# Analog_Telem.net
KiCad netlist of a schematic drawn in Altium Designer
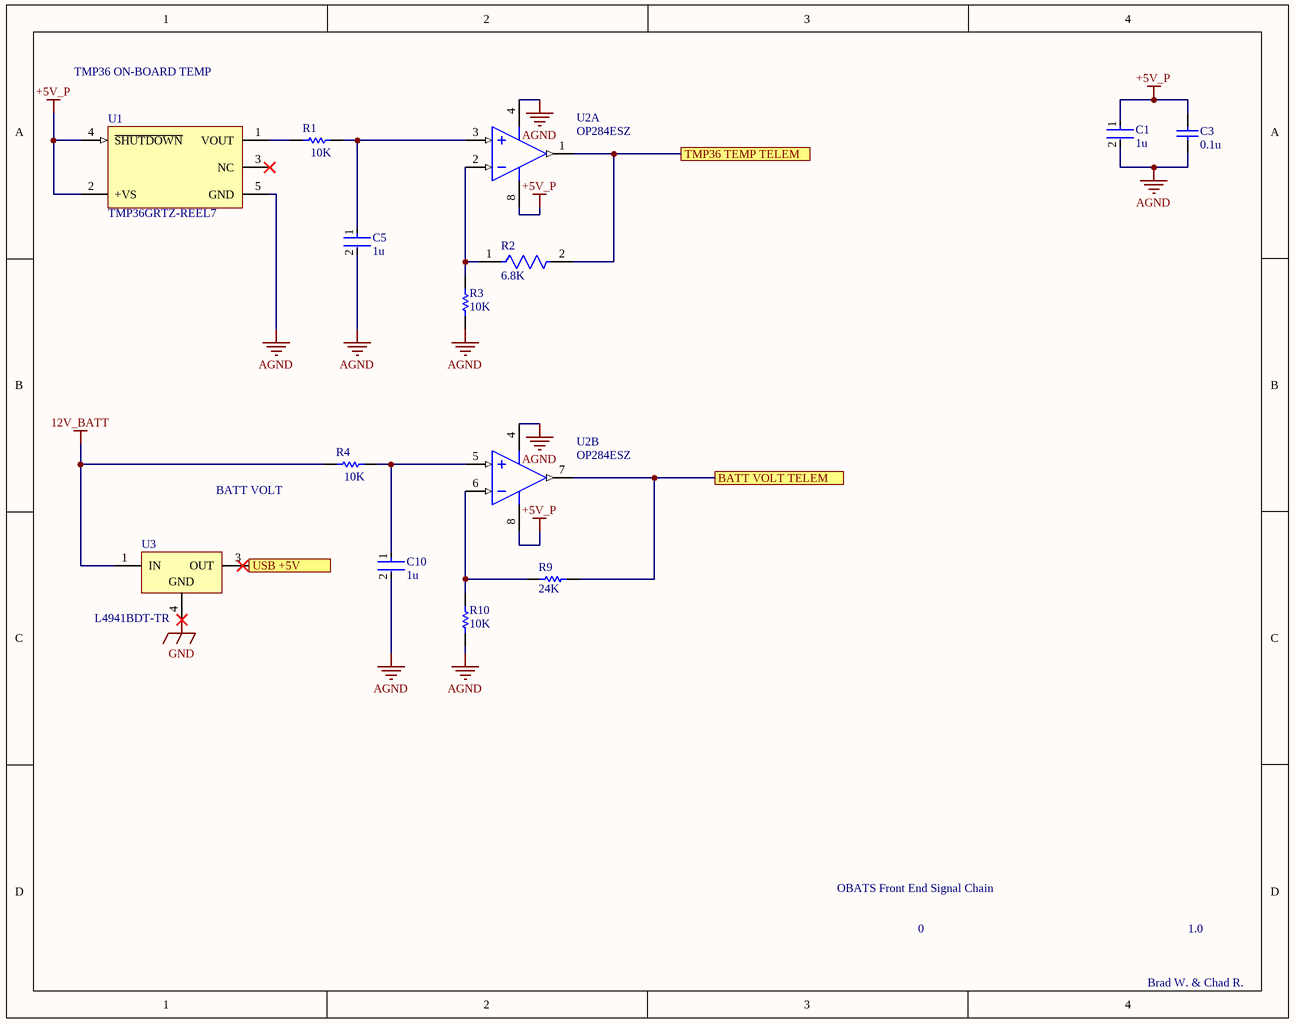
[diagram p0: Analog_Telem.SchDoc]

(export (version "E")
  (design (tool "Eeschema 10.0.6"))
  (components
    (comp (ref "C1")
      (value "1u")
      (footprint "FP-CL31-IPC_B")
      (description "Cap Ceramic 1uF 50V X7R ±10% SMD 1206 +125°C Embossed T/R")
      (fields (field (name "VOLTAGE") "50V") (field (name "TOLERANCE") "10%"))
      (libsource (lib "Altium Content Vault") (part "b4654b650e69147ec39a6b967a45e02"))
    )
    (comp (ref "C3")
      (value "0.1u")
      (footprint "CAPC1206(3216)130_M")
      (description "CAP 100nF 100V ±20% 1206 (3216 Metric) Thickness 1.3mm SMD")
      (fields (field (name "TOLERANCE") "Â±20%"))
      (libsource (lib "Altium Content Vault") (part "CAP"))
    )
    (comp (ref "C5")
      (value "1u")
      (footprint "FP-CL31-IPC_B")
      (description "Cap Ceramic 1uF 50V X7R ±10% SMD 1206 +125°C Embossed T/R")
      (fields (field (name "VOLTAGE") "50V") (field (name "TOLERANCE") "10%"))
      (libsource (lib "Altium Content Vault") (part "b4654b650e69147ec39a6b967a45e02"))
    )
    (comp (ref "C10")
      (value "1u")
      (footprint "FP-CL31-IPC_B")
      (description "Cap Ceramic 1uF 50V X7R ±10% SMD 1206 +125°C Embossed T/R")
      (fields (field (name "VOLTAGE") "50V") (field (name "TOLERANCE") "10%"))
      (libsource (lib "Altium Content Vault") (part "b4654b650e69147ec39a6b967a45e02"))
    )
    (comp (ref "R1")
      (value "10K")
      (footprint "RESC3116X65X45ML10T20")
      (fields (field (name "MANUFACTURER") "Yageo") (field (name "PART NUMBER") "AC1206FR-0710KL"))
      (libsource (lib "Altium Content Vault") (part "RES"))
    )
    (comp (ref "R2")
      (value "6.8K")
      (footprint "FP-AC1206-MFG")
      (description "RES SMD 6.8K OHM 1% 1/4W 1206")
      (fields
        (field (name "OCTOPART") "https://octopart.com/ac1206fr-076k8l-yageo-26041203")
        (field (name "MANUFACTURER PART NUMBER") "AC1206FR-076K8L")
      )
      (libsource (lib "Altium Content Vault") (part "1029c3af85768c4190bb7ad29bc67b5"))
    )
    (comp (ref "R3")
      (value "10K")
      (footprint "RESC3116X65X45ML10T20")
      (fields (field (name "MANUFACTURER") "Yageo") (field (name "PART NUMBER") "AC1206FR-0710KL"))
      (libsource (lib "Altium Content Vault") (part "RES"))
    )
    (comp (ref "R4")
      (value "10K")
      (footprint "RESC3116X65X45ML10T20")
      (fields (field (name "MANUFACTURER") "Yageo") (field (name "PART NUMBER") "AC1206FR-0710KL"))
      (libsource (lib "Altium Content Vault") (part "RES"))
    )
    (comp (ref "R9")
      (value "24K")
      (footprint "RESC2013X70X40ML20T20")
      (fields (field (name "MANUFACTURER") "Panasonic") (field (name "PART NUMBER") "ERJ6ENF2402V"))
      (libsource (lib "Altium Content Vault") (part "RES"))
    )
    (comp (ref "R10")
      (value "10K")
      (footprint "RESC3116X65X45ML10T20")
      (fields (field (name "MANUFACTURER") "Yageo") (field (name "PART NUMBER") "AC1206FR-0710KL"))
      (libsource (lib "Altium Content Vault") (part "RES"))
    )
    (comp (ref "U1")
      (value "TMP36GRTZ-REEL7")
      (footprint "ADI-RJ-5_L")
      (description "Voltage Output Temperature Sensor, 2.7 to 5.5 V Supply, Industrial, 5-pin SOT23 (RJ-5), Reel")
      (fields (field (name "MANUFACTURER") "Analog Devices"))
      (libsource (lib "Altium Content Vault") (part "ADI-TMP3X-RJ-5"))
    )
    (comp (ref "U2")
      (value "OP284ESZ")
      (footprint "ADI-R-8_L")
      (fields (field (name "GENERIC PART NUMBER") "OP284") (field (name "MANUFACTURER") "Analog Devices"))
      (libsource (lib "Altium Content Vault") (part "ADI-OP29X-R-8"))
    )
    (comp (ref "U3")
      (value "L4941BDT-TR")
      (footprint "TO-252_L")
      (description "1A Very Low Drop Regulator, 3-Pin DPAK, Tape and Reel")
      (libsource (lib "Altium Content Vault") (part "PM-REG-L4940-SOT3"))
    )
  )
  (nets
    (net (code "1") (name "+5V_P") (class "Default")
      (node (ref "C1") (pin "1") (pinfunction "1_1") (pintype "passive"))
      (node (ref "C3") (pin "2") (pinfunction "2_2") (pintype "passive"))
      (node (ref "U1") (pin "2") (pinfunction "+VS_2") (pintype "power_in"))
      (node (ref "U1") (pin "4") (pinfunction "~{SHUTDOWN}_4") (pintype "input"))
      (node (ref "U2") (pin "8") (pinfunction "+V_8") (pintype "power_in"))
    )
    (net (code "2") (name "/BATT VOLT TELEM") (class "Default")
      (node (ref "R9") (pin "2") (pinfunction "2_2") (pintype "passive"))
      (node (ref "U2") (pin "7") (pinfunction "OUT_B_7") (pintype "output"))
    )
    (net (code "3") (name "/TMP36 TEMP TELEM") (class "Default")
      (node (ref "R2") (pin "2") (pinfunction "2_2") (pintype "passive"))
      (node (ref "U2") (pin "1") (pinfunction "OUT_A_1") (pintype "output"))
    )
    (net (code "4") (name "/USB +5V") (class "Default")
      (node (ref "U3") (pin "3") (pinfunction "OUT_3") (pintype "power_in"))
    )
    (net (code "5") (name "12V_BATT") (class "Default")
      (node (ref "R4") (pin "1") (pinfunction "1_1") (pintype "passive"))
      (node (ref "U3") (pin "1") (pinfunction "IN_1") (pintype "power_in"))
    )
    (net (code "6") (name "AGND") (class "Default")
      (node (ref "C1") (pin "2") (pinfunction "2_2") (pintype "passive"))
      (node (ref "C10") (pin "2") (pinfunction "2_2") (pintype "passive"))
      (node (ref "C3") (pin "1") (pinfunction "1_1") (pintype "passive"))
      (node (ref "C5") (pin "2") (pinfunction "2_2") (pintype "passive"))
      (node (ref "R10") (pin "1") (pinfunction "1_1") (pintype "passive"))
      (node (ref "R3") (pin "1") (pinfunction "1_1") (pintype "passive"))
      (node (ref "U1") (pin "5") (pinfunction "GND_5") (pintype "power_in"))
      (node (ref "U2") (pin "4") (pinfunction "-V_4") (pintype "power_in"))
    )
    (net (code "7") (name "GND") (class "Default")
      (node (ref "U3") (pin "4") (pinfunction "GND_4") (pintype "power_in"))
    )
    (net (code "8") (name "Net-(U1-VOUT)") (class "Default")
      (node (ref "R1") (pin "1") (pinfunction "1_1") (pintype "passive"))
      (node (ref "U1") (pin "1") (pinfunction "VOUT_1") (pintype "tri_state"))
    )
    (net (code "9") (name "Net-(U2A-+IN_A)") (class "Default")
      (node (ref "C5") (pin "1") (pinfunction "1_1") (pintype "passive"))
      (node (ref "R1") (pin "2") (pinfunction "2_2") (pintype "passive"))
      (node (ref "U2") (pin "3") (pinfunction "+IN_A_3") (pintype "input"))
    )
    (net (code "10") (name "Net-(U2A--IN_A)") (class "Default")
      (node (ref "R2") (pin "1") (pinfunction "1_1") (pintype "passive"))
      (node (ref "R3") (pin "2") (pinfunction "2_2") (pintype "passive"))
      (node (ref "U2") (pin "2") (pinfunction "-IN_A_2") (pintype "input"))
    )
    (net (code "11") (name "Net-(U2B-+IN_B)") (class "Default")
      (node (ref "C10") (pin "1") (pinfunction "1_1") (pintype "passive"))
      (node (ref "R4") (pin "2") (pinfunction "2_2") (pintype "passive"))
      (node (ref "U2") (pin "5") (pinfunction "+IN_B_5") (pintype "input"))
    )
    (net (code "12") (name "Net-(U2B--IN_B)") (class "Default")
      (node (ref "R10") (pin "2") (pinfunction "2_2") (pintype "passive"))
      (node (ref "R9") (pin "1") (pinfunction "1_1") (pintype "passive"))
      (node (ref "U2") (pin "6") (pinfunction "-IN_B_6") (pintype "input"))
    )
    (net (code "13") (name "unconnected-(U1-NC-Pad3)") (class "Default")
      (node (ref "U1") (pin "3") (pinfunction "NC_3") (pintype "passive+no_connect"))
    )
  )
)
